# LED_CONV_SIG.net
KiCad netlist of a schematic drawn in Altium Designer
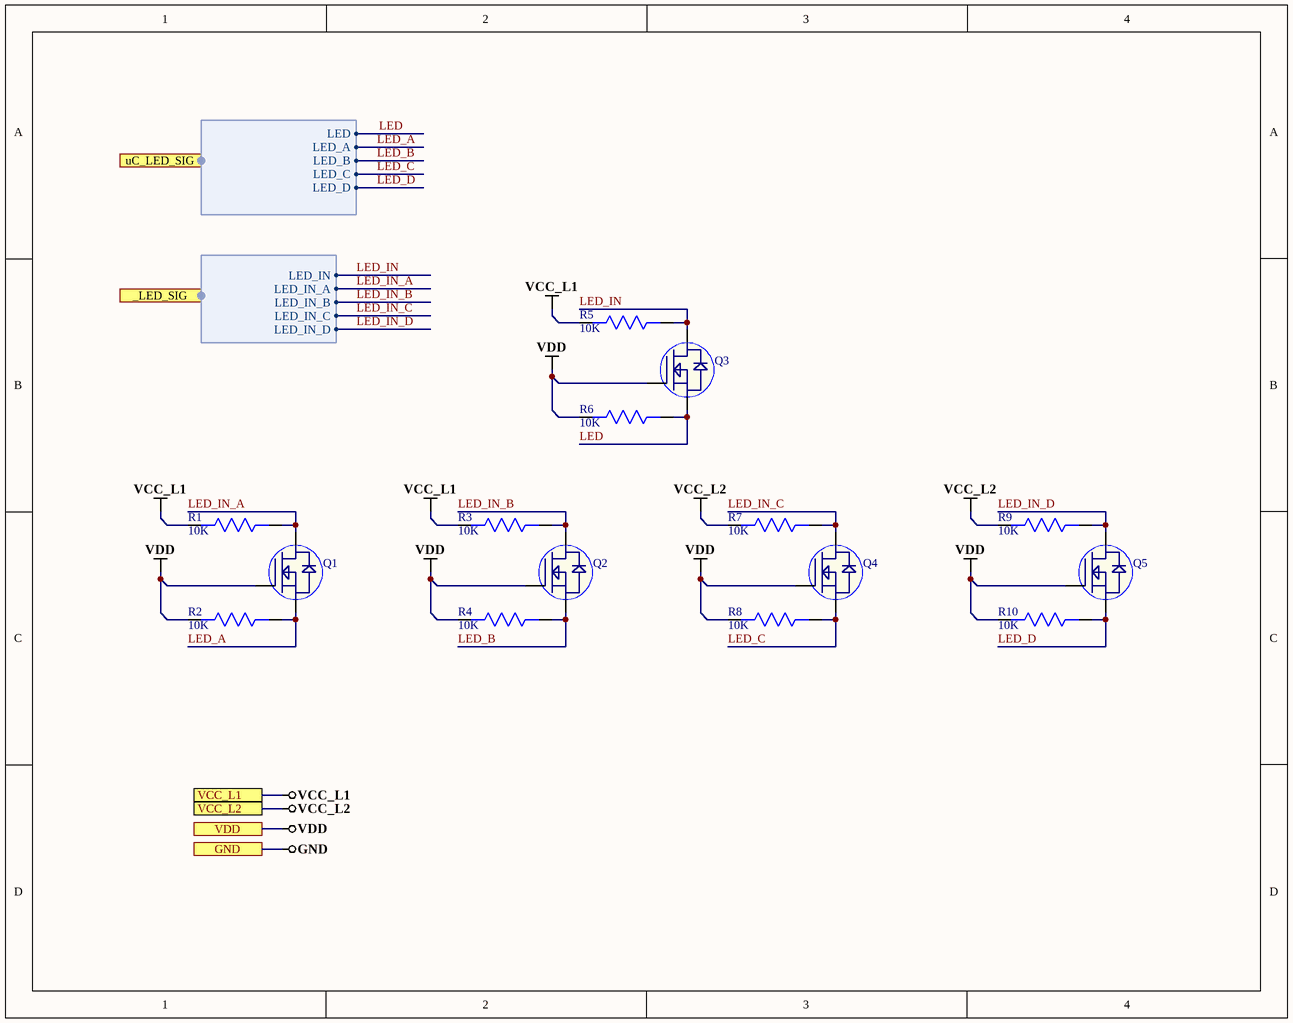
[diagram p0: LED_CONV_SIG.SchDoc]

(export (version "E")
  (design (tool "Eeschema 10.0.6"))
  (components
    (comp (ref "Q1")
      (value "BSS138LT1G")
      (footprint "SOT23-3")
      (description "MOSFET N-CH 50V 200MA SOT-23")
      (fields (field (name "MANUFACTURER") "ON Semiconductor"))
      (libsource (lib "TT_IntLib") (part "BSS138LT1G"))
    )
    (comp (ref "Q2")
      (value "BSS138LT1G")
      (footprint "SOT23-3")
      (description "MOSFET N-CH 50V 200MA SOT-23")
      (fields (field (name "MANUFACTURER") "ON Semiconductor"))
      (libsource (lib "TT_IntLib") (part "BSS138LT1G"))
    )
    (comp (ref "Q3")
      (value "BSS138LT1G")
      (footprint "SOT23-3")
      (description "MOSFET N-CH 50V 200MA SOT-23")
      (fields (field (name "MANUFACTURER") "ON Semiconductor"))
      (libsource (lib "TT_IntLib") (part "BSS138LT1G"))
    )
    (comp (ref "Q4")
      (value "BSS138LT1G")
      (footprint "SOT23-3")
      (description "MOSFET N-CH 50V 200MA SOT-23")
      (fields (field (name "MANUFACTURER") "ON Semiconductor"))
      (libsource (lib "TT_IntLib") (part "BSS138LT1G"))
    )
    (comp (ref "Q5")
      (value "BSS138LT1G")
      (footprint "SOT23-3")
      (description "MOSFET N-CH 50V 200MA SOT-23")
      (fields (field (name "MANUFACTURER") "ON Semiconductor"))
      (libsource (lib "TT_IntLib") (part "BSS138LT1G"))
    )
    (comp (ref "R1")
      (value "10K")
      (footprint "Res-0201")
      (description "GENERAL 0201 11% REEL (7INCH)")
      (fields
        (field (name "MANUFACTURER") "Yageo")
        (field (name "MANUFACTURER PART NUMBER") "RC0201FR-0710KL")
      )
      (libsource (lib "TT_IntLib") (part "RC0201FR-0710KL"))
    )
    (comp (ref "R2")
      (value "10K")
      (footprint "Res-0201")
      (description "GENERAL 0201 11% REEL (7INCH)")
      (fields
        (field (name "MANUFACTURER") "Yageo")
        (field (name "MANUFACTURER PART NUMBER") "RC0201FR-0710KL")
      )
      (libsource (lib "TT_IntLib") (part "RC0201FR-0710KL"))
    )
    (comp (ref "R3")
      (value "10K")
      (footprint "Res-0201")
      (description "GENERAL 0201 11% REEL (7INCH)")
      (fields
        (field (name "MANUFACTURER") "Yageo")
        (field (name "MANUFACTURER PART NUMBER") "RC0201FR-0710KL")
      )
      (libsource (lib "TT_IntLib") (part "RC0201FR-0710KL"))
    )
    (comp (ref "R4")
      (value "10K")
      (footprint "Res-0201")
      (description "GENERAL 0201 11% REEL (7INCH)")
      (fields
        (field (name "MANUFACTURER") "Yageo")
        (field (name "MANUFACTURER PART NUMBER") "RC0201FR-0710KL")
      )
      (libsource (lib "TT_IntLib") (part "RC0201FR-0710KL"))
    )
    (comp (ref "R5")
      (value "10K")
      (footprint "Res-0201")
      (description "GENERAL 0201 11% REEL (7INCH)")
      (fields
        (field (name "MANUFACTURER") "Yageo")
        (field (name "MANUFACTURER PART NUMBER") "RC0201FR-0710KL")
      )
      (libsource (lib "TT_IntLib") (part "RC0201FR-0710KL"))
    )
    (comp (ref "R6")
      (value "10K")
      (footprint "Res-0201")
      (description "GENERAL 0201 11% REEL (7INCH)")
      (fields
        (field (name "MANUFACTURER") "Yageo")
        (field (name "MANUFACTURER PART NUMBER") "RC0201FR-0710KL")
      )
      (libsource (lib "TT_IntLib") (part "RC0201FR-0710KL"))
    )
    (comp (ref "R7")
      (value "10K")
      (footprint "Res-0201")
      (description "GENERAL 0201 11% REEL (7INCH)")
      (fields
        (field (name "MANUFACTURER") "Yageo")
        (field (name "MANUFACTURER PART NUMBER") "RC0201FR-0710KL")
      )
      (libsource (lib "TT_IntLib") (part "RC0201FR-0710KL"))
    )
    (comp (ref "R8")
      (value "10K")
      (footprint "Res-0201")
      (description "GENERAL 0201 11% REEL (7INCH)")
      (fields
        (field (name "MANUFACTURER") "Yageo")
        (field (name "MANUFACTURER PART NUMBER") "RC0201FR-0710KL")
      )
      (libsource (lib "TT_IntLib") (part "RC0201FR-0710KL"))
    )
    (comp (ref "R9")
      (value "10K")
      (footprint "Res-0201")
      (description "GENERAL 0201 11% REEL (7INCH)")
      (fields
        (field (name "MANUFACTURER") "Yageo")
        (field (name "MANUFACTURER PART NUMBER") "RC0201FR-0710KL")
      )
      (libsource (lib "TT_IntLib") (part "RC0201FR-0710KL"))
    )
    (comp (ref "R10")
      (value "10K")
      (footprint "Res-0201")
      (description "GENERAL 0201 11% REEL (7INCH)")
      (fields
        (field (name "MANUFACTURER") "Yageo")
        (field (name "MANUFACTURER PART NUMBER") "RC0201FR-0710KL")
      )
      (libsource (lib "TT_IntLib") (part "RC0201FR-0710KL"))
    )
  )
  (nets
    (net (code "3") (name "/LED") (class "Default")
      (node (ref "Q3") (pin "2") (pinfunction "S_2") (pintype "passive"))
      (node (ref "R6") (pin "2") (pintype "passive"))
    )
    (net (code "4") (name "/LED_A") (class "Default")
      (node (ref "Q1") (pin "2") (pinfunction "S_2") (pintype "passive"))
      (node (ref "R2") (pin "2") (pintype "passive"))
    )
    (net (code "5") (name "/LED_B") (class "Default")
      (node (ref "Q2") (pin "2") (pinfunction "S_2") (pintype "passive"))
      (node (ref "R4") (pin "2") (pintype "passive"))
    )
    (net (code "6") (name "/LED_C") (class "Default")
      (node (ref "Q4") (pin "2") (pinfunction "S_2") (pintype "passive"))
      (node (ref "R8") (pin "2") (pintype "passive"))
    )
    (net (code "7") (name "/LED_D") (class "Default")
      (node (ref "Q5") (pin "2") (pinfunction "S_2") (pintype "passive"))
      (node (ref "R10") (pin "2") (pintype "passive"))
    )
    (net (code "8") (name "/LED_IN") (class "Default")
      (node (ref "Q3") (pin "3") (pinfunction "D_3") (pintype "passive"))
      (node (ref "R5") (pin "2") (pintype "passive"))
    )
    (net (code "9") (name "/LED_IN_A") (class "Default")
      (node (ref "Q1") (pin "3") (pinfunction "D_3") (pintype "passive"))
      (node (ref "R1") (pin "2") (pintype "passive"))
    )
    (net (code "10") (name "/LED_IN_B") (class "Default")
      (node (ref "Q2") (pin "3") (pinfunction "D_3") (pintype "passive"))
      (node (ref "R3") (pin "2") (pintype "passive"))
    )
    (net (code "11") (name "/LED_IN_C") (class "Default")
      (node (ref "Q4") (pin "3") (pinfunction "D_3") (pintype "passive"))
      (node (ref "R7") (pin "2") (pintype "passive"))
    )
    (net (code "12") (name "/LED_IN_D") (class "Default")
      (node (ref "Q5") (pin "3") (pinfunction "D_3") (pintype "passive"))
      (node (ref "R9") (pin "2") (pintype "passive"))
    )
    (net (code "16") (name "VCC_L1") (class "Default")
      (node (ref "R1") (pin "1") (pintype "passive"))
      (node (ref "R3") (pin "1") (pintype "passive"))
      (node (ref "R5") (pin "1") (pintype "passive"))
    )
    (net (code "17") (name "VCC_L2") (class "Default")
      (node (ref "R7") (pin "1") (pintype "passive"))
      (node (ref "R9") (pin "1") (pintype "passive"))
    )
    (net (code "18") (name "VDD") (class "Default")
      (node (ref "Q1") (pin "1") (pinfunction "G_1") (pintype "passive"))
      (node (ref "Q2") (pin "1") (pinfunction "G_1") (pintype "passive"))
      (node (ref "Q3") (pin "1") (pinfunction "G_1") (pintype "passive"))
      (node (ref "Q4") (pin "1") (pinfunction "G_1") (pintype "passive"))
      (node (ref "Q5") (pin "1") (pinfunction "G_1") (pintype "passive"))
      (node (ref "R10") (pin "1") (pintype "passive"))
      (node (ref "R2") (pin "1") (pintype "passive"))
      (node (ref "R4") (pin "1") (pintype "passive"))
      (node (ref "R6") (pin "1") (pintype "passive"))
      (node (ref "R8") (pin "1") (pintype "passive"))
    )
  )
)
